# MOSFETs.net
KiCad netlist of a schematic drawn in Altium Designer
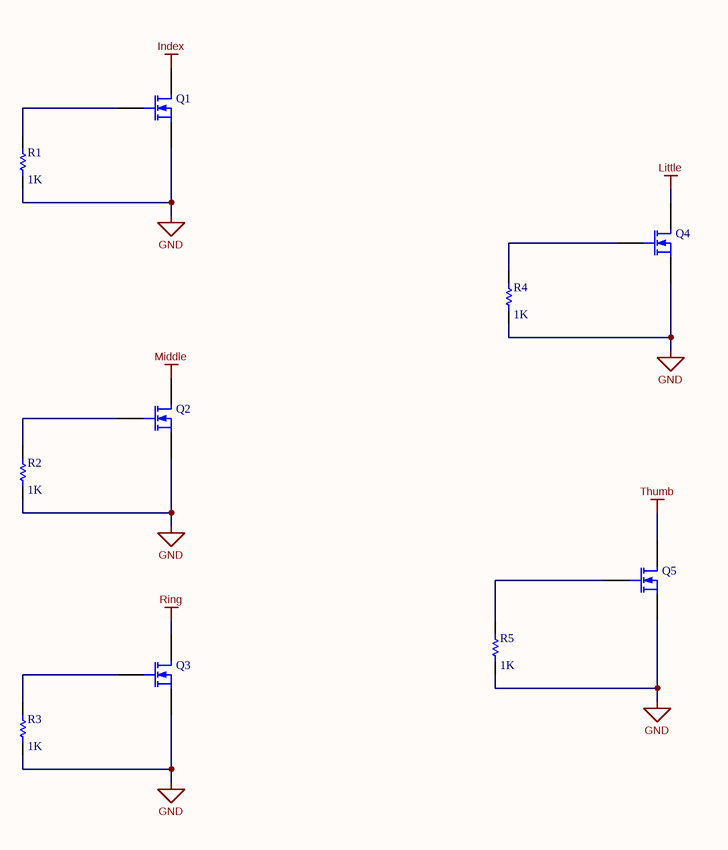
[diagram p0: MOSFETs.SchDoc]

(export (version "E")
  (design (tool "Eeschema 10.0.6"))
  (components
    (comp (ref "Q1")
      (value "MOSFET-N")
      (footprint "E3")
      (description "N-Channel MOSFET")
      (fields (field (name "PUBLISHER") "Altium Limited"))
      (libsource (lib "FE Miscellaneous Devices") (part "MOSFET-N"))
    )
    (comp (ref "Q2")
      (value "MOSFET-N")
      (footprint "E3")
      (description "N-Channel MOSFET")
      (fields (field (name "PUBLISHER") "Altium Limited"))
      (libsource (lib "FE Miscellaneous Devices") (part "MOSFET-N"))
    )
    (comp (ref "Q3")
      (value "MOSFET-N")
      (footprint "E3")
      (description "N-Channel MOSFET")
      (fields (field (name "PUBLISHER") "Altium Limited"))
      (libsource (lib "FE Miscellaneous Devices") (part "MOSFET-N"))
    )
    (comp (ref "Q4")
      (value "MOSFET-N")
      (footprint "E3")
      (description "N-Channel MOSFET")
      (fields (field (name "PUBLISHER") "Altium Limited"))
      (libsource (lib "FE Miscellaneous Devices") (part "MOSFET-N"))
    )
    (comp (ref "Q5")
      (value "MOSFET-N")
      (footprint "E3")
      (description "N-Channel MOSFET")
      (fields (field (name "PUBLISHER") "Altium Limited"))
      (libsource (lib "FE Miscellaneous Devices") (part "MOSFET-N"))
    )
    (comp (ref "R1")
      (value "1K")
      (footprint "AXIAL-0.3")
      (description "Resistor")
      (fields (field (name "Comment") "Res1") (field (name "PUBLISHER") "Altium Limited"))
      (libsource (lib "FE Miscellaneous Devices") (part "Res1"))
    )
    (comp (ref "R2")
      (value "1K")
      (footprint "AXIAL-0.3")
      (description "Resistor")
      (fields (field (name "Comment") "Res1") (field (name "PUBLISHER") "Altium Limited"))
      (libsource (lib "FE Miscellaneous Devices") (part "Res1"))
    )
    (comp (ref "R3")
      (value "1K")
      (footprint "AXIAL-0.3")
      (description "Resistor")
      (fields (field (name "Comment") "Res1") (field (name "PUBLISHER") "Altium Limited"))
      (libsource (lib "FE Miscellaneous Devices") (part "Res1"))
    )
    (comp (ref "R4")
      (value "1K")
      (footprint "AXIAL-0.3")
      (description "Resistor")
      (fields (field (name "Comment") "Res1") (field (name "PUBLISHER") "Altium Limited"))
      (libsource (lib "FE Miscellaneous Devices") (part "Res1"))
    )
    (comp (ref "R5")
      (value "1K")
      (footprint "AXIAL-0.3")
      (description "Resistor")
      (fields (field (name "Comment") "Res1") (field (name "PUBLISHER") "Altium Limited"))
      (libsource (lib "FE Miscellaneous Devices") (part "Res1"))
    )
  )
  (nets
    (net (code "1") (name "GND") (class "Default")
      (node (ref "Q1") (pin "3") (pinfunction "S_3") (pintype "passive"))
      (node (ref "Q2") (pin "3") (pinfunction "S_3") (pintype "passive"))
      (node (ref "Q3") (pin "3") (pinfunction "S_3") (pintype "passive"))
      (node (ref "Q4") (pin "3") (pinfunction "S_3") (pintype "passive"))
      (node (ref "Q5") (pin "3") (pinfunction "S_3") (pintype "passive"))
      (node (ref "R1") (pin "1") (pinfunction "1_1") (pintype "passive"))
      (node (ref "R2") (pin "1") (pinfunction "1_1") (pintype "passive"))
      (node (ref "R3") (pin "1") (pinfunction "1_1") (pintype "passive"))
      (node (ref "R4") (pin "1") (pinfunction "1_1") (pintype "passive"))
      (node (ref "R5") (pin "1") (pinfunction "1_1") (pintype "passive"))
    )
    (net (code "2") (name "Index") (class "Default")
      (node (ref "Q1") (pin "1") (pinfunction "D_1") (pintype "passive"))
    )
    (net (code "3") (name "Little") (class "Default")
      (node (ref "Q4") (pin "1") (pinfunction "D_1") (pintype "passive"))
    )
    (net (code "4") (name "Middle") (class "Default")
      (node (ref "Q2") (pin "1") (pinfunction "D_1") (pintype "passive"))
    )
    (net (code "5") (name "Net-(Q1-G)") (class "Default")
      (node (ref "Q1") (pin "2") (pinfunction "G_2") (pintype "passive"))
      (node (ref "R1") (pin "2") (pinfunction "2_2") (pintype "passive"))
    )
    (net (code "6") (name "Net-(Q2-G)") (class "Default")
      (node (ref "Q2") (pin "2") (pinfunction "G_2") (pintype "passive"))
      (node (ref "R2") (pin "2") (pinfunction "2_2") (pintype "passive"))
    )
    (net (code "7") (name "Net-(Q3-G)") (class "Default")
      (node (ref "Q3") (pin "2") (pinfunction "G_2") (pintype "passive"))
      (node (ref "R3") (pin "2") (pinfunction "2_2") (pintype "passive"))
    )
    (net (code "8") (name "Net-(Q4-G)") (class "Default")
      (node (ref "Q4") (pin "2") (pinfunction "G_2") (pintype "passive"))
      (node (ref "R4") (pin "2") (pinfunction "2_2") (pintype "passive"))
    )
    (net (code "9") (name "Net-(Q5-G)") (class "Default")
      (node (ref "Q5") (pin "2") (pinfunction "G_2") (pintype "passive"))
      (node (ref "R5") (pin "2") (pinfunction "2_2") (pintype "passive"))
    )
    (net (code "10") (name "Ring") (class "Default")
      (node (ref "Q3") (pin "1") (pinfunction "D_1") (pintype "passive"))
    )
    (net (code "11") (name "Thumb") (class "Default")
      (node (ref "Q5") (pin "1") (pinfunction "D_1") (pintype "passive"))
    )
  )
)
